# RN-42.net
KiCad netlist of a schematic drawn in EAGLE
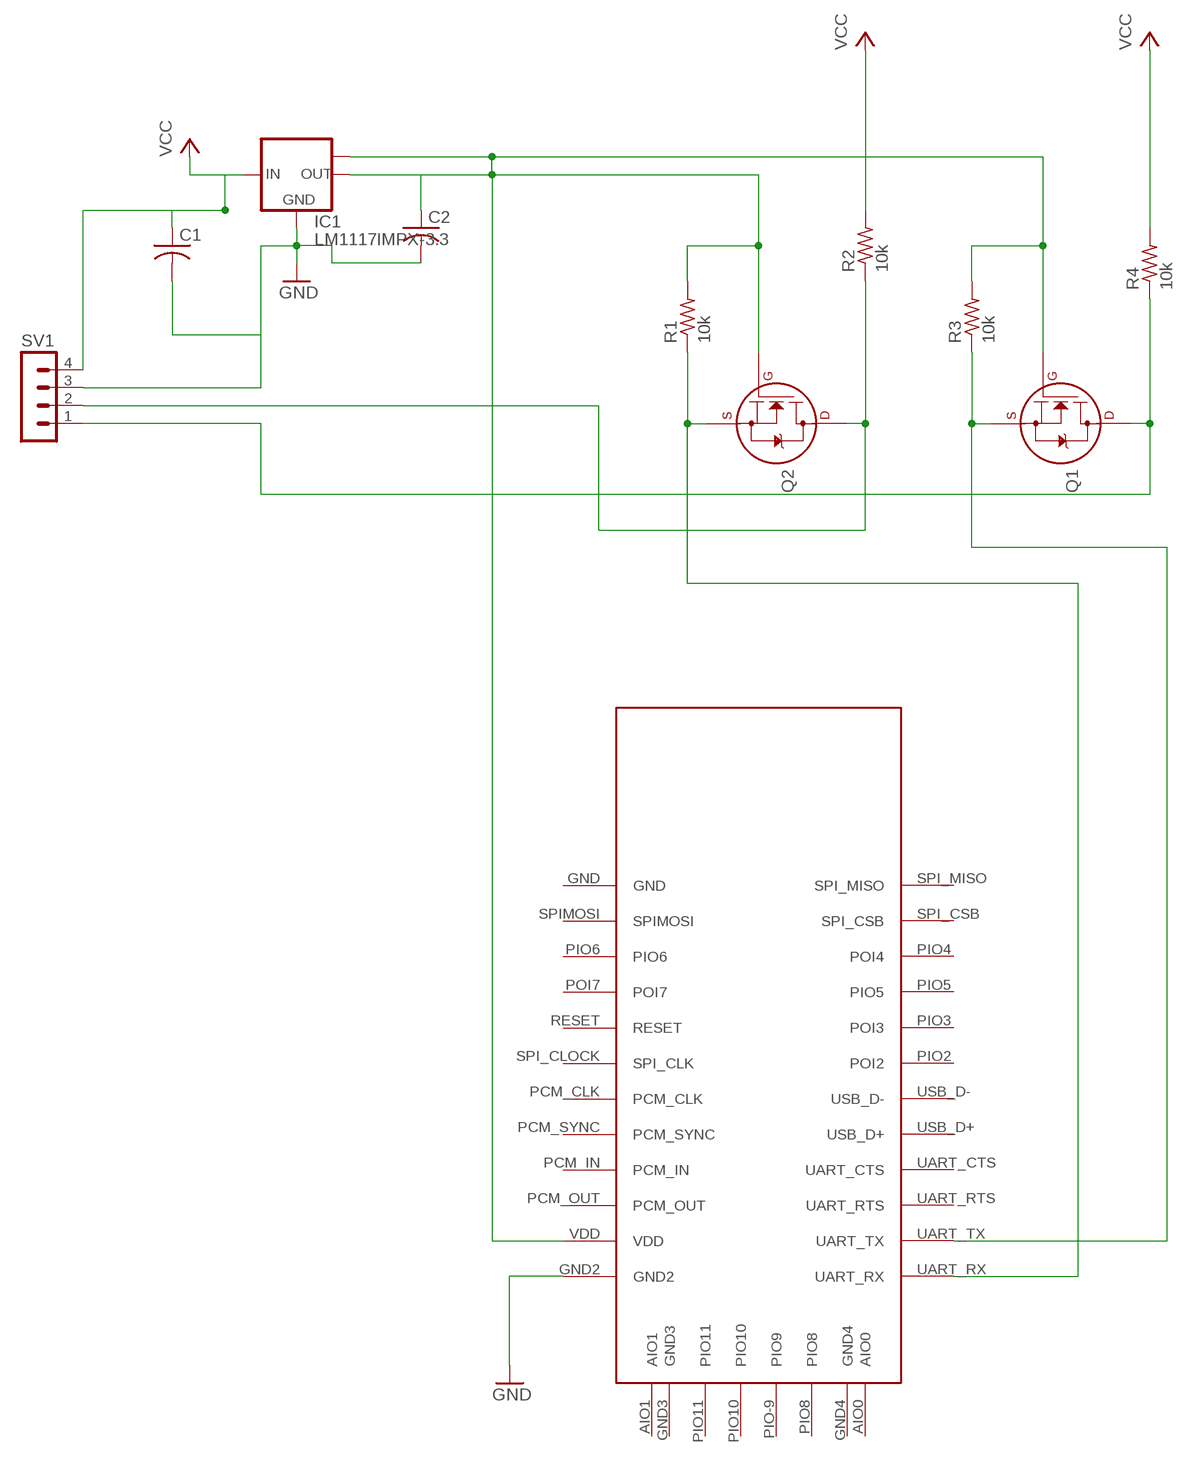
[diagram p0: schematic, sheet 1]

(export (version "E")
  (design (tool "Eeschema 10.0.6"))
  (components
    (comp (ref "C1")
      (value "C-USC0805")
      (footprint "eagle-import:C0805")
      (libsource (lib "eagle-import") (part "C-USC0805"))
    )
    (comp (ref "C2")
      (value "C-USC0805")
      (footprint "eagle-import:C0805")
      (libsource (lib "eagle-import") (part "C-USC0805"))
    )
    (comp (ref "IC1")
      (value "LM1117IMPX-3.3")
      (footprint "eagle-import:SOT223")
      (libsource (lib "eagle-import") (part "LM1117IMPX-3.3"))
    )
    (comp (ref "Q1")
      (value "2N7002_SOT23")
      (footprint "eagle-import:SOT-23")
      (libsource (lib "eagle-import") (part "2N700_SOT232"))
    )
    (comp (ref "Q2")
      (value "2N7002_SOT23")
      (footprint "eagle-import:SOT-23")
      (libsource (lib "eagle-import") (part "2N700_SOT232"))
    )
    (comp (ref "R1")
      (value "10k")
      (footprint "eagle-import:M0805")
      (libsource (lib "eagle-import") (part "R-US_M0805"))
    )
    (comp (ref "R2")
      (value "10k")
      (footprint "eagle-import:M0805")
      (libsource (lib "eagle-import") (part "R-US_M0805"))
    )
    (comp (ref "R3")
      (value "10k")
      (footprint "eagle-import:M0805")
      (libsource (lib "eagle-import") (part "R-US_M0805"))
    )
    (comp (ref "R4")
      (value "10k")
      (footprint "eagle-import:M0805")
      (libsource (lib "eagle-import") (part "R-US_M0805"))
    )
    (comp (ref "SV1")
      (value "MA04-1")
      (footprint "eagle-import:MA04-1")
      (libsource (lib "eagle-import") (part "MA04-1"))
    )
    (comp (ref "U$1")
      (value "RN-42")
      (footprint "eagle-import:RN-42")
      (libsource (lib "eagle-import") (part "RN-42"))
    )
  )
  (nets
    (net (code "1") (name "GND") (class "Default")
      (node (ref "C1") (pin "2") (pinfunction "2_2") (pintype "passive"))
      (node (ref "C2") (pin "2") (pinfunction "2_2") (pintype "passive"))
      (node (ref "IC1") (pin "1") (pinfunction "GND_1") (pintype "input"))
      (node (ref "SV1") (pin "3") (pinfunction "3_3") (pintype "passive"))
      (node (ref "U$1") (pin "GND2") (pinfunction "GND2_GND2") (pintype "bidirectional"))
    )
    (net (code "2") (name "Net-(IC1-OUT)") (class "Default")
      (node (ref "C2") (pin "1") (pinfunction "1_1") (pintype "passive"))
      (node (ref "IC1") (pin "2") (pinfunction "OUT_2") (pintype "passive"))
      (node (ref "IC1") (pin "TAB") (pinfunction "OUT1_TAB") (pintype "passive"))
      (node (ref "Q1") (pin "1") (pinfunction "G_1") (pintype "tri_state"))
      (node (ref "Q2") (pin "1") (pinfunction "G_1") (pintype "tri_state"))
      (node (ref "R1") (pin "2") (pinfunction "2_2") (pintype "passive"))
      (node (ref "R3") (pin "2") (pinfunction "2_2") (pintype "passive"))
      (node (ref "U$1") (pin "VDD") (pinfunction "VDD_VDD") (pintype "bidirectional"))
    )
    (net (code "3") (name "Net-(Q1-D)") (class "Default")
      (node (ref "Q1") (pin "3") (pinfunction "D_3") (pintype "bidirectional"))
      (node (ref "R4") (pin "1") (pinfunction "1_1") (pintype "passive"))
      (node (ref "SV1") (pin "1") (pinfunction "1_1") (pintype "passive"))
    )
    (net (code "4") (name "Net-(Q1-S)") (class "Default")
      (node (ref "Q1") (pin "2") (pinfunction "S_2") (pintype "bidirectional"))
      (node (ref "R3") (pin "1") (pinfunction "1_1") (pintype "passive"))
      (node (ref "U$1") (pin "UART_TX") (pinfunction "UART_TX_UART_TX") (pintype "bidirectional"))
    )
    (net (code "5") (name "Net-(Q2-D)") (class "Default")
      (node (ref "Q2") (pin "3") (pinfunction "D_3") (pintype "bidirectional"))
      (node (ref "R2") (pin "1") (pinfunction "1_1") (pintype "passive"))
      (node (ref "SV1") (pin "2") (pinfunction "2_2") (pintype "passive"))
    )
    (net (code "6") (name "Net-(Q2-S)") (class "Default")
      (node (ref "Q2") (pin "2") (pinfunction "S_2") (pintype "bidirectional"))
      (node (ref "R1") (pin "1") (pinfunction "1_1") (pintype "passive"))
      (node (ref "U$1") (pin "UART_RX") (pinfunction "UART_RX_UART_RX") (pintype "bidirectional"))
    )
    (net (code "7") (name "VCC") (class "Default")
      (node (ref "C1") (pin "1") (pinfunction "1_1") (pintype "passive"))
      (node (ref "IC1") (pin "3") (pinfunction "IN_3") (pintype "input"))
      (node (ref "R2") (pin "2") (pinfunction "2_2") (pintype "passive"))
      (node (ref "R4") (pin "2") (pinfunction "2_2") (pintype "passive"))
      (node (ref "SV1") (pin "4") (pinfunction "4_4") (pintype "passive"))
    )
    (net (code "8") (name "unconnected-(U$1-PIO9-PadPIO-9)") (class "Default")
      (node (ref "U$1") (pin "PIO-9") (pinfunction "PIO9_PIO-9") (pintype "bidirectional"))
    )
    (net (code "9") (name "unconnected-(U$1-POI2-PadPIO2)") (class "Default")
      (node (ref "U$1") (pin "PIO2") (pinfunction "POI2_PIO2") (pintype "bidirectional"))
    )
    (net (code "10") (name "unconnected-(U$1-POI3-PadPIO3)") (class "Default")
      (node (ref "U$1") (pin "PIO3") (pinfunction "POI3_PIO3") (pintype "bidirectional"))
    )
    (net (code "11") (name "unconnected-(U$1-POI4-PadPIO4)") (class "Default")
      (node (ref "U$1") (pin "PIO4") (pinfunction "POI4_PIO4") (pintype "bidirectional"))
    )
    (net (code "12") (name "unconnected-(U$1-PadAIO0)") (class "Default")
      (node (ref "U$1") (pin "AIO0") (pinfunction "AIO0_AIO0") (pintype "bidirectional"))
    )
    (net (code "13") (name "unconnected-(U$1-PadAIO1)") (class "Default")
      (node (ref "U$1") (pin "AIO1") (pinfunction "AIO1_AIO1") (pintype "bidirectional"))
    )
    (net (code "14") (name "unconnected-(U$1-PadGND)") (class "Default")
      (node (ref "U$1") (pin "GND") (pinfunction "GND_GND") (pintype "bidirectional"))
    )
    (net (code "15") (name "unconnected-(U$1-PadGND3)") (class "Default")
      (node (ref "U$1") (pin "GND3") (pinfunction "GND3_GND3") (pintype "bidirectional"))
    )
    (net (code "16") (name "unconnected-(U$1-PadGND4)") (class "Default")
      (node (ref "U$1") (pin "GND4") (pinfunction "GND4_GND4") (pintype "bidirectional"))
    )
    (net (code "17") (name "unconnected-(U$1-PadPCM_CLK)") (class "Default")
      (node (ref "U$1") (pin "PCM_CLK") (pinfunction "PCM_CLK_PCM_CLK") (pintype "bidirectional"))
    )
    (net (code "18") (name "unconnected-(U$1-PadPCM_IN)") (class "Default")
      (node (ref "U$1") (pin "PCM_IN") (pinfunction "PCM_IN_PCM_IN") (pintype "bidirectional"))
    )
    (net (code "19") (name "unconnected-(U$1-PadPCM_OUT)") (class "Default")
      (node (ref "U$1") (pin "PCM_OUT") (pinfunction "PCM_OUT_PCM_OUT") (pintype "bidirectional"))
    )
    (net (code "20") (name "unconnected-(U$1-PadPCM_SYNC)") (class "Default")
      (node (ref "U$1") (pin "PCM_SYNC") (pinfunction "PCM_SYNC_PCM_SYNC") (pintype "bidirectional"))
    )
    (net (code "21") (name "unconnected-(U$1-PadPIO5)") (class "Default")
      (node (ref "U$1") (pin "PIO5") (pinfunction "PIO5_PIO5") (pintype "bidirectional"))
    )
    (net (code "22") (name "unconnected-(U$1-PadPIO6)") (class "Default")
      (node (ref "U$1") (pin "PIO6") (pinfunction "PIO6_PIO6") (pintype "bidirectional"))
    )
    (net (code "23") (name "unconnected-(U$1-PadPIO8)") (class "Default")
      (node (ref "U$1") (pin "PIO8") (pinfunction "PIO8_PIO8") (pintype "bidirectional"))
    )
    (net (code "24") (name "unconnected-(U$1-PadPIO10)") (class "Default")
      (node (ref "U$1") (pin "PIO10") (pinfunction "PIO10_PIO10") (pintype "bidirectional"))
    )
    (net (code "25") (name "unconnected-(U$1-PadPIO11)") (class "Default")
      (node (ref "U$1") (pin "PIO11") (pinfunction "PIO11_PIO11") (pintype "bidirectional"))
    )
    (net (code "26") (name "unconnected-(U$1-PadPOI7)") (class "Default")
      (node (ref "U$1") (pin "POI7") (pinfunction "POI7_POI7") (pintype "bidirectional"))
    )
    (net (code "27") (name "unconnected-(U$1-PadRESET)") (class "Default")
      (node (ref "U$1") (pin "RESET") (pinfunction "RESET_RESET") (pintype "bidirectional"))
    )
    (net (code "28") (name "unconnected-(U$1-PadSPIMOSI)") (class "Default")
      (node (ref "U$1") (pin "SPIMOSI") (pinfunction "SPIMOSI_SPIMOSI") (pintype "bidirectional"))
    )
    (net (code "29") (name "unconnected-(U$1-PadSPI_CSB)") (class "Default")
      (node (ref "U$1") (pin "SPI_CSB") (pinfunction "SPI_CSB_SPI_CSB") (pintype "bidirectional"))
    )
    (net (code "30") (name "unconnected-(U$1-PadSPI_MISO)") (class "Default")
      (node (ref "U$1") (pin "SPI_MISO") (pinfunction "SPI_MISO_SPI_MISO") (pintype "bidirectional"))
    )
    (net (code "31") (name "unconnected-(U$1-PadUART_CTS)") (class "Default")
      (node (ref "U$1") (pin "UART_CTS") (pinfunction "UART_CTS_UART_CTS") (pintype "bidirectional"))
    )
    (net (code "32") (name "unconnected-(U$1-PadUART_RTS)") (class "Default")
      (node (ref "U$1") (pin "UART_RTS") (pinfunction "UART_RTS_UART_RTS") (pintype "bidirectional"))
    )
    (net (code "33") (name "unconnected-(U$1-PadUSB_D+)") (class "Default")
      (node (ref "U$1") (pin "USB_D+") (pinfunction "USB_D+_USB_D+") (pintype "bidirectional"))
    )
    (net (code "34") (name "unconnected-(U$1-PadUSB_D-)") (class "Default")
      (node (ref "U$1") (pin "USB_D-") (pinfunction "USB_D-_USB_D-") (pintype "bidirectional"))
    )
    (net (code "35") (name "unconnected-(U$1-SPI_CLK-PadSPI_CLOCK)") (class "Default")
      (node (ref "U$1") (pin "SPI_CLOCK") (pinfunction "SPI_CLK_SPI_CLOCK") (pintype "bidirectional"))
    )
  )
)
